# Class_D_Amp.net
KiCad netlist of a schematic drawn in EasyEDA Pro
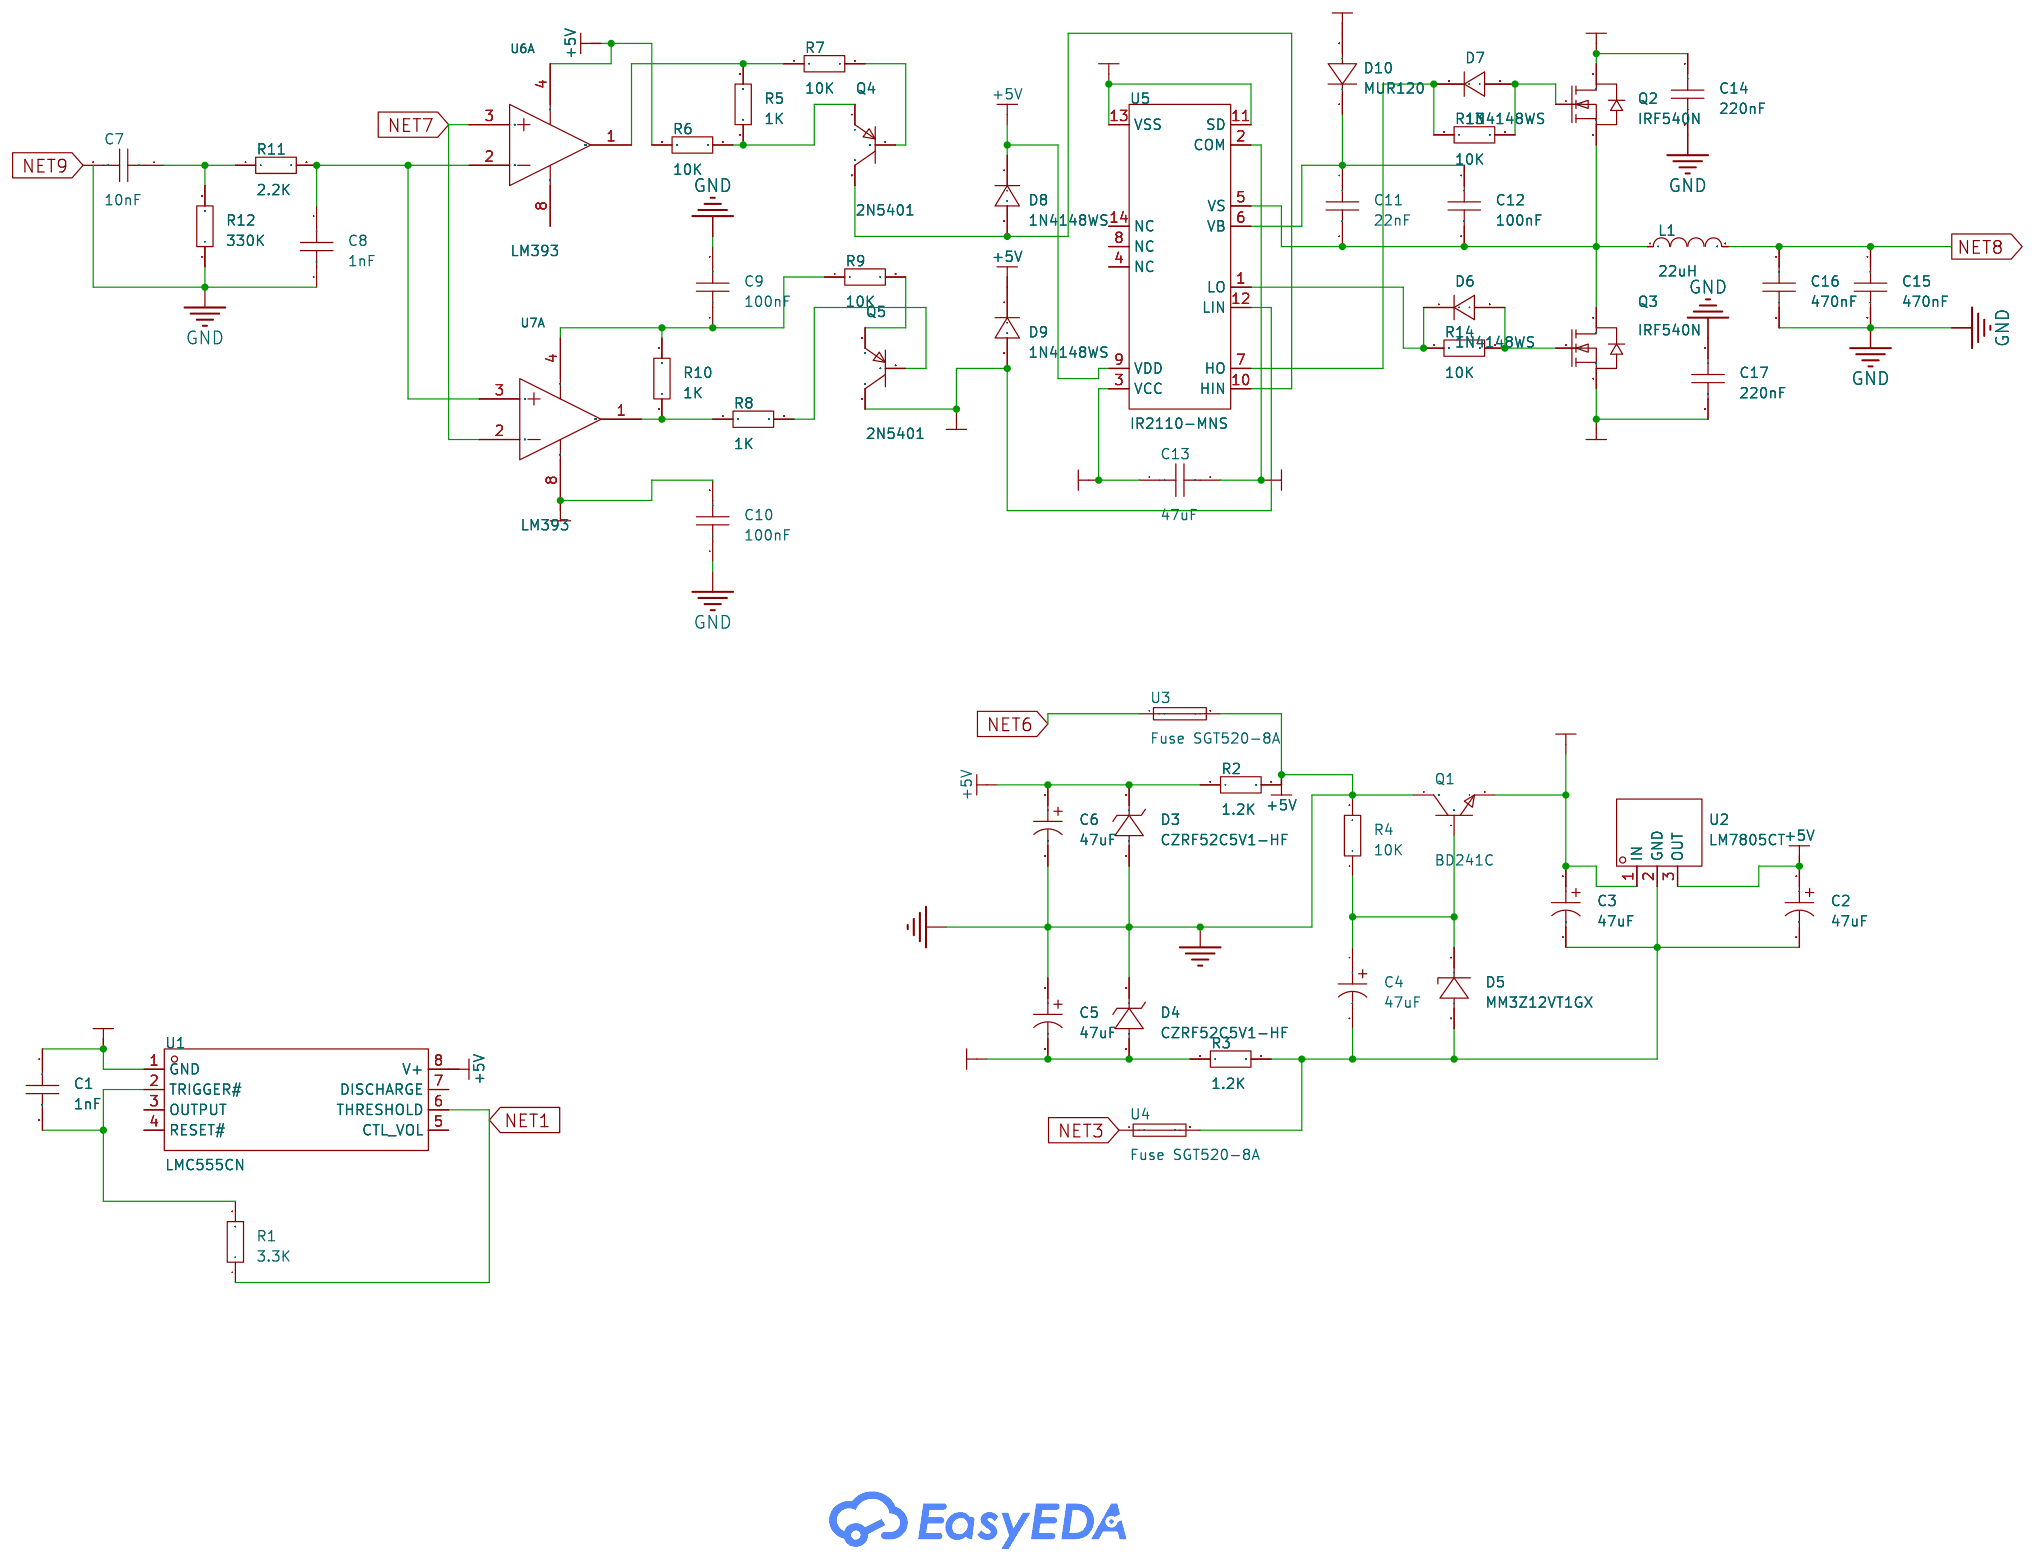
[diagram p0: schematic sheet]

(export (version "E")
  (design (tool "Eeschema 10.0.6"))
  (components
    (comp (ref "C1") (value "1nF") (footprint "easyedapro:C0603") (libsource (lib "easyedapro") (part "CAP")))
    (comp (ref "C2")
      (value "47uF")
      (footprint "easyedapro:CAP-TH_BD6.3-P2.50-D0.6-FD")
      (fields (field (name "Manufacturer Part") "ERA63V47M6X12") (field (name "Manufacturer") "JIERR(捷而瑞)"))
      (libsource (lib "easyedapro") (part "ERA63V47M6X12"))
    )
    (comp (ref "C3")
      (value "47uF")
      (footprint "easyedapro:CAP-TH_BD6.3-P2.50-D0.6-FD")
      (fields (field (name "Manufacturer Part") "ERA63V47M6X12") (field (name "Manufacturer") "JIERR(捷而瑞)"))
      (libsource (lib "easyedapro") (part "ERA63V47M6X12"))
    )
    (comp (ref "C4")
      (value "47uF")
      (footprint "easyedapro:CAP-TH_BD6.3-P2.50-D0.6-FD")
      (fields (field (name "Manufacturer Part") "ERA63V47M6X12") (field (name "Manufacturer") "JIERR(捷而瑞)"))
      (libsource (lib "easyedapro") (part "ERA63V47M6X12"))
    )
    (comp (ref "C5")
      (value "47uF")
      (footprint "easyedapro:CAP-TH_BD6.3-P2.50-D0.6-FD")
      (fields (field (name "Manufacturer Part") "ERA63V47M6X12") (field (name "Manufacturer") "JIERR(捷而瑞)"))
      (libsource (lib "easyedapro") (part "ERA63V47M6X12"))
    )
    (comp (ref "C6")
      (value "47uF")
      (footprint "easyedapro:CAP-TH_BD6.3-P2.50-D0.6-FD")
      (fields (field (name "Manufacturer Part") "ERA63V47M6X12") (field (name "Manufacturer") "JIERR(捷而瑞)"))
      (libsource (lib "easyedapro") (part "ERA63V47M6X12"))
    )
    (comp (ref "C7")
      (value "10nF")
      (footprint "easyedapro:C0603")
      (libsource (lib "easyedapro") (part "CAP"))
    )
    (comp (ref "C8") (value "1nF") (footprint "easyedapro:C0603") (libsource (lib "easyedapro") (part "CAP")))
    (comp (ref "C9")
      (value "100nF")
      (footprint "easyedapro:C0603")
      (libsource (lib "easyedapro") (part "CAP"))
    )
    (comp (ref "C10")
      (value "100nF")
      (footprint "easyedapro:C0603")
      (libsource (lib "easyedapro") (part "CAP"))
    )
    (comp (ref "C11")
      (value "22nF")
      (footprint "easyedapro:C0603")
      (libsource (lib "easyedapro") (part "CAP"))
    )
    (comp (ref "C12")
      (value "100nF")
      (footprint "easyedapro:C0603")
      (libsource (lib "easyedapro") (part "CAP"))
    )
    (comp (ref "C13")
      (value "47uF")
      (footprint "easyedapro:C0603")
      (libsource (lib "easyedapro") (part "CAP"))
    )
    (comp (ref "C14")
      (value "220nF")
      (footprint "easyedapro:C0603")
      (libsource (lib "easyedapro") (part "CAP"))
    )
    (comp (ref "C15")
      (value "470nF")
      (footprint "easyedapro:C0603")
      (libsource (lib "easyedapro") (part "CAP"))
    )
    (comp (ref "C16")
      (value "470nF")
      (footprint "easyedapro:C0603")
      (libsource (lib "easyedapro") (part "CAP"))
    )
    (comp (ref "C17")
      (value "220nF")
      (footprint "easyedapro:C0603")
      (libsource (lib "easyedapro") (part "CAP"))
    )
    (comp (ref "D3")
      (value "CZRF52C5V1-HF")
      (footprint "easyedapro:SOD-323F_L2.5-W1.2-LS2.5-RD")
      (fields (field (name "Manufacturer") "Comchip(典琦)"))
      (libsource (lib "easyedapro") (part "CZRF52C5V1-HF"))
    )
    (comp (ref "D4")
      (value "CZRF52C5V1-HF")
      (footprint "easyedapro:SOD-323F_L2.5-W1.2-LS2.5-RD")
      (fields (field (name "Manufacturer") "Comchip(典琦)"))
      (libsource (lib "easyedapro") (part "CZRF52C5V1-HF"))
    )
    (comp (ref "D5")
      (value "MM3Z12VT1GX")
      (footprint "easyedapro:SOD-323_L1.8-W1.3-LS2.5-RD")
      (fields (field (name "Manufacturer") "Nexperia(安世)"))
      (libsource (lib "easyedapro") (part "MM3Z12VT1GX"))
    )
    (comp (ref "D6")
      (value "1N4148WS")
      (footprint "easyedapro:SOD-323_L1.8-W1.3-LS2.5-RD")
      (fields (field (name "Manufacturer") "CJ(江苏长电/长晶)"))
      (libsource (lib "easyedapro") (part "1N4148WS T4"))
    )
    (comp (ref "D7")
      (value "1N4148WS")
      (footprint "easyedapro:SOD-323_L1.8-W1.3-LS2.5-RD")
      (fields (field (name "Manufacturer") "CJ(江苏长电/长晶)"))
      (libsource (lib "easyedapro") (part "1N4148WS T4"))
    )
    (comp (ref "D8")
      (value "1N4148WS")
      (footprint "easyedapro:SOD-323_L1.8-W1.3-LS2.5-RD")
      (fields (field (name "Manufacturer") "CJ(江苏长电/长晶)"))
      (libsource (lib "easyedapro") (part "1N4148WS T4"))
    )
    (comp (ref "D9")
      (value "1N4148WS")
      (footprint "easyedapro:SOD-323_L1.8-W1.3-LS2.5-RD")
      (fields (field (name "Manufacturer") "CJ(江苏长电/长晶)"))
      (libsource (lib "easyedapro") (part "1N4148WS T4"))
    )
    (comp (ref "D10")
      (value "MUR120")
      (footprint "easyedapro:DO-41_BD2.4-L4.7-P8.70-D0.9-RD")
      (fields (field (name "Manufacturer") "YANGJIE(扬杰)"))
      (libsource (lib "easyedapro") (part "MUR120-C1-0000"))
    )
    (comp (ref "L1") (value "22uH") (footprint "easyedapro:L0603") (libsource (lib "easyedapro") (part "电感")))
    (comp (ref "Q1")
      (value "BD241C")
      (footprint "easyedapro:TO-220-3_L10.0-W4.5-P2.54-L")
      (fields (field (name "Manufacturer") "SPTECH(深圳质超)"))
      (libsource (lib "easyedapro") (part "BD241C"))
    )
    (comp (ref "Q2")
      (value "IRF540N")
      (footprint "easyedapro:TO-220-3_L10.2-W4.6-P2.54-L")
      (fields (field (name "Manufacturer") "DOINGTER(杜因特)"))
      (libsource (lib "easyedapro") (part "IRF540N_C41430602"))
    )
    (comp (ref "Q3")
      (value "IRF540N")
      (footprint "easyedapro:TO-220-3_L10.2-W4.6-P2.54-L")
      (fields (field (name "Manufacturer") "DOINGTER(杜因特)"))
      (libsource (lib "easyedapro") (part "IRF540N_C41430602"))
    )
    (comp (ref "Q4")
      (value "2N5401")
      (footprint "easyedapro:TO-92-3_L4.5-W3.5-P1.27-L")
      (fields (field (name "Manufacturer") "Slkor(萨科微)"))
      (libsource (lib "easyedapro") (part "2N5401_C2936033"))
    )
    (comp (ref "Q5")
      (value "2N5401")
      (footprint "easyedapro:TO-92-3_L4.5-W3.5-P1.27-L")
      (fields (field (name "Manufacturer") "Slkor(萨科微)"))
      (libsource (lib "easyedapro") (part "2N5401_C2936033"))
    )
    (comp (ref "R1")
      (value "3.3K")
      (footprint "easyedapro:R0603")
      (libsource (lib "easyedapro") (part "Res"))
    )
    (comp (ref "R2")
      (value "1.2K")
      (footprint "easyedapro:R0603")
      (libsource (lib "easyedapro") (part "Res"))
    )
    (comp (ref "R3")
      (value "1.2K")
      (footprint "easyedapro:R0603")
      (libsource (lib "easyedapro") (part "Res"))
    )
    (comp (ref "R4") (value "10K") (footprint "easyedapro:R0603") (libsource (lib "easyedapro") (part "Res")))
    (comp (ref "R5") (value "1K") (footprint "easyedapro:R0603") (libsource (lib "easyedapro") (part "Res")))
    (comp (ref "R6") (value "10K") (footprint "easyedapro:R0603") (libsource (lib "easyedapro") (part "Res")))
    (comp (ref "R7") (value "10K") (footprint "easyedapro:R0603") (libsource (lib "easyedapro") (part "Res")))
    (comp (ref "R8") (value "1K") (footprint "easyedapro:R0603") (libsource (lib "easyedapro") (part "Res")))
    (comp (ref "R9") (value "10K") (footprint "easyedapro:R0603") (libsource (lib "easyedapro") (part "Res")))
    (comp (ref "R10") (value "1K") (footprint "easyedapro:R0603") (libsource (lib "easyedapro") (part "Res")))
    (comp (ref "R11")
      (value "2.2K")
      (footprint "easyedapro:R0603")
      (libsource (lib "easyedapro") (part "Res"))
    )
    (comp (ref "R12")
      (value "330K")
      (footprint "easyedapro:R0603")
      (libsource (lib "easyedapro") (part "Res"))
    )
    (comp (ref "R13")
      (value "10K")
      (footprint "easyedapro:R0603")
      (libsource (lib "easyedapro") (part "Res"))
    )
    (comp (ref "R14")
      (value "10K")
      (footprint "easyedapro:R0603")
      (libsource (lib "easyedapro") (part "Res"))
    )
    (comp (ref "U1")
      (value "LMC555CN")
      (footprint "easyedapro:DIP-8_L9.7-W6.4-P2.54-LS7.6-BL")
      (description "Operating Temperature:-40°C~+85°C Operating Temperature:-40°C~+85°C")
      (fields (field (name "Manufacturer") "TI(德州仪器)"))
      (libsource (lib "easyedapro") (part "LMC555CN"))
    )
    (comp (ref "U2")
      (value "LM7805CT")
      (footprint "easyedapro:TO-220-3_L10.0-W4.5-P2.54-L")
      (libsource (lib "easyedapro") (part "LM7805CT"))
    )
    (comp (ref "U3")
      (value "Fuse SGT520-8A")
      (footprint "easyedapro:FUSE-SMD_L20.0-W5.2")
      (fields (field (name "Manufacturer") "SET(赛尔特)"))
      (libsource (lib "easyedapro") (part "FUSE SGT520-8A"))
    )
    (comp (ref "U4")
      (value "Fuse SGT520-8A")
      (footprint "easyedapro:FUSE-SMD_L20.0-W5.2")
      (fields (field (name "Manufacturer") "SET(赛尔特)"))
      (libsource (lib "easyedapro") (part "FUSE SGT520-8A"))
    )
    (comp (ref "U5")
      (value "IR2110-MNS")
      (footprint "easyedapro:PDIP-14_L19.2-W6.6-P2.54-LS7.6-BL")
      (fields (field (name "Manufacturer") "minos(迈诺斯)"))
      (libsource (lib "easyedapro") (part "IR2110-MNS"))
    )
    (comp (ref "U6")
      (value "LM393")
      (footprint "easyedapro:SOP-8_L4.9-W3.9-P1.27-LS6.0-BL")
      (fields (field (name "Manufacturer") "MSKSEMI(美森科)"))
      (libsource (lib "easyedapro") (part "LM393_C5252905"))
    )
    (comp (ref "U7")
      (value "LM393")
      (footprint "easyedapro:SOP-8_L4.9-W3.9-P1.27-LS6.0-BL")
      (fields (field (name "Manufacturer") "MSKSEMI(美森科)"))
      (libsource (lib "easyedapro") (part "LM393_C5252905"))
    )
  )
  (nets
    (net (code "1") (name "+5V") (class "Default")
      (node (ref "C2") (pin "1") (pinfunction "1_1") (pintype "input"))
      (node (ref "C5") (pin "1") (pinfunction "1_1") (pintype "input"))
      (node (ref "C6") (pin "1") (pinfunction "1_1") (pintype "input"))
      (node (ref "C6") (pin "2") (pinfunction "2_2") (pintype "input"))
      (node (ref "D3") (pin "1") (pinfunction "K_1") (pintype "unspecified"))
      (node (ref "D3") (pin "2") (pinfunction "A_2") (pintype "unspecified"))
      (node (ref "D4") (pin "1") (pinfunction "K_1") (pintype "unspecified"))
      (node (ref "D8") (pin "1") (pinfunction "K_1") (pintype "unspecified"))
      (node (ref "D9") (pin "1") (pinfunction "K_1") (pintype "unspecified"))
      (node (ref "Q1") (pin "2") (pinfunction "C_2") (pintype "input"))
      (node (ref "R2") (pin "1") (pinfunction "1_1") (pintype "input"))
      (node (ref "R2") (pin "2") (pinfunction "2_2") (pintype "input"))
      (node (ref "R4") (pin "2") (pinfunction "2_2") (pintype "input"))
      (node (ref "R6") (pin "1") (pinfunction "1_1") (pintype "input"))
      (node (ref "U1") (pin "8") (pinfunction "V+_8") (pintype "unspecified"))
      (node (ref "U2") (pin "3") (pinfunction "OUT_3") (pintype "unspecified"))
      (node (ref "U3") (pin "2") (pinfunction "2_2") (pintype "unspecified"))
      (node (ref "U5") (pin "9") (pinfunction "VDD_9") (pintype "unspecified"))
      (node (ref "U6") (pin "4") (pinfunction "VEE_4") (pintype "input"))
    )
    (net (code "2") (name "+12V") (class "Default")
      (node (ref "C13") (pin "1") (pinfunction "1_1") (pintype "input"))
      (node (ref "C3") (pin "1") (pinfunction "1_1") (pintype "input"))
      (node (ref "D10") (pin "2") (pinfunction "A_2") (pintype "unspecified"))
      (node (ref "Q1") (pin "3") (pinfunction "E_3") (pintype "input"))
      (node (ref "U2") (pin "1") (pinfunction "IN_1") (pintype "unspecified"))
      (node (ref "U5") (pin "3") (pinfunction "VCC_3") (pintype "unspecified"))
    )
    (net (code "3") (name "+30V") (class "Default")
      (node (ref "C14") (pin "1") (pinfunction "1_1") (pintype "input"))
      (node (ref "Q2") (pin "2") (pinfunction "D_2") (pintype "unspecified"))
    )
    (net (code "4") (name "-5V") (class "Default")
      (node (ref "C1") (pin "1") (pinfunction "1_1") (pintype "input"))
      (node (ref "C10") (pin "2") (pinfunction "2_2") (pintype "input"))
      (node (ref "C5") (pin "2") (pinfunction "2_2") (pintype "input"))
      (node (ref "D4") (pin "2") (pinfunction "A_2") (pintype "unspecified"))
      (node (ref "R3") (pin "1") (pinfunction "1_1") (pintype "input"))
      (node (ref "U1") (pin "1") (pinfunction "GND_1") (pintype "unspecified"))
      (node (ref "U7") (pin "8") (pinfunction "VCC_8") (pintype "input"))
    )
    (net (code "5") (name "-30V") (class "Default")
      (node (ref "C13") (pin "2") (pinfunction "2_2") (pintype "input"))
      (node (ref "C17") (pin "2") (pinfunction "2_2") (pintype "input"))
      (node (ref "D9") (pin "2") (pinfunction "A_2") (pintype "unspecified"))
      (node (ref "Q3") (pin "3") (pinfunction "S_3") (pintype "unspecified"))
      (node (ref "Q5") (pin "3") (pinfunction "C_3") (pintype "input"))
      (node (ref "U5") (pin "11") (pinfunction "SD_11") (pintype "unspecified"))
      (node (ref "U5") (pin "12") (pinfunction "LIN_12") (pintype "unspecified"))
      (node (ref "U5") (pin "13") (pinfunction "VSS_13") (pintype "unspecified"))
      (node (ref "U5") (pin "2") (pinfunction "COM_2") (pintype "unspecified"))
    )
    (net (code "6") (name "GND") (class "Default")
      (node (ref "C10") (pin "1") (pinfunction "1_1") (pintype "input"))
      (node (ref "C14") (pin "2") (pinfunction "2_2") (pintype "input"))
      (node (ref "C15") (pin "2") (pinfunction "2_2") (pintype "input"))
      (node (ref "C16") (pin "2") (pinfunction "2_2") (pintype "input"))
      (node (ref "C17") (pin "1") (pinfunction "1_1") (pintype "input"))
      (node (ref "C8") (pin "2") (pinfunction "2_2") (pintype "input"))
      (node (ref "C9") (pin "2") (pinfunction "2_2") (pintype "input"))
      (node (ref "R12") (pin "1") (pinfunction "1_1") (pintype "input"))
    )
    (net (code "7") (name "NET1") (class "Default")
      (node (ref "R1") (pin "1") (pinfunction "1_1") (pintype "input"))
      (node (ref "U1") (pin "6") (pinfunction "THRESHOLD_6") (pintype "unspecified"))
    )
    (net (code "8") (name "NET3") (class "Default")
      (node (ref "U4") (pin "1") (pinfunction "1_1") (pintype "unspecified"))
    )
    (net (code "9") (name "NET6") (class "Default")
      (node (ref "U3") (pin "1") (pinfunction "1_1") (pintype "unspecified"))
    )
    (net (code "10") (name "NET7") (class "Default")
      (node (ref "U6") (pin "3") (pinfunction "1IN+_3") (pintype "input"))
      (node (ref "U7") (pin "2") (pinfunction "1IN-_2") (pintype "input"))
    )
    (net (code "11") (name "NET8") (class "Default")
      (node (ref "C15") (pin "1") (pinfunction "1_1") (pintype "input"))
      (node (ref "C16") (pin "1") (pinfunction "1_1") (pintype "input"))
      (node (ref "L1") (pin "2") (pinfunction "2_2") (pintype "input"))
    )
    (net (code "12") (name "NET9") (class "Default")
      (node (ref "C7") (pin "2") (pinfunction "2_2") (pintype "input"))
    )
    (net (code "13") (name "Net-(C7-Pad1)") (class "Default")
      (node (ref "C7") (pin "1") (pinfunction "1_1") (pintype "input"))
      (node (ref "R11") (pin "1") (pinfunction "1_1") (pintype "input"))
      (node (ref "R12") (pin "2") (pinfunction "2_2") (pintype "input"))
    )
    (net (code "14") (name "Net-(D5-A)") (class "Default")
      (node (ref "C2") (pin "2") (pinfunction "2_2") (pintype "input"))
      (node (ref "C3") (pin "2") (pinfunction "2_2") (pintype "input"))
      (node (ref "C4") (pin "2") (pinfunction "2_2") (pintype "input"))
      (node (ref "D5") (pin "2") (pinfunction "A_2") (pintype "unspecified"))
      (node (ref "R3") (pin "2") (pinfunction "2_2") (pintype "input"))
      (node (ref "U2") (pin "2") (pinfunction "GND_2") (pintype "unspecified"))
      (node (ref "U4") (pin "2") (pinfunction "2_2") (pintype "unspecified"))
    )
    (net (code "15") (name "Net-(D5-K)") (class "Default")
      (node (ref "C4") (pin "1") (pinfunction "1_1") (pintype "input"))
      (node (ref "D5") (pin "1") (pinfunction "K_1") (pintype "unspecified"))
      (node (ref "Q1") (pin "1") (pinfunction "B_1") (pintype "input"))
      (node (ref "R4") (pin "1") (pinfunction "1_1") (pintype "input"))
    )
    (net (code "16") (name "Net-(D6-A)") (class "Default")
      (node (ref "D6") (pin "2") (pinfunction "A_2") (pintype "unspecified"))
      (node (ref "Q3") (pin "1") (pinfunction "G_1") (pintype "unspecified"))
      (node (ref "R14") (pin "2") (pinfunction "2_2") (pintype "input"))
    )
    (net (code "17") (name "Net-(D6-K)") (class "Default")
      (node (ref "D6") (pin "1") (pinfunction "K_1") (pintype "unspecified"))
      (node (ref "R14") (pin "1") (pinfunction "1_1") (pintype "input"))
      (node (ref "U5") (pin "1") (pinfunction "LO_1") (pintype "unspecified"))
    )
    (net (code "18") (name "Net-(D7-A)") (class "Default")
      (node (ref "D7") (pin "2") (pinfunction "A_2") (pintype "unspecified"))
      (node (ref "Q2") (pin "1") (pinfunction "G_1") (pintype "unspecified"))
      (node (ref "R13") (pin "2") (pinfunction "2_2") (pintype "input"))
    )
    (net (code "19") (name "Net-(D7-K)") (class "Default")
      (node (ref "D7") (pin "1") (pinfunction "K_1") (pintype "unspecified"))
      (node (ref "R13") (pin "1") (pinfunction "1_1") (pintype "input"))
      (node (ref "U5") (pin "7") (pinfunction "HO_7") (pintype "unspecified"))
    )
    (net (code "20") (name "Net-(D8-A)") (class "Default")
      (node (ref "D8") (pin "2") (pinfunction "A_2") (pintype "unspecified"))
      (node (ref "Q4") (pin "3") (pinfunction "C_3") (pintype "input"))
      (node (ref "U5") (pin "10") (pinfunction "HIN_10") (pintype "unspecified"))
    )
    (net (code "21") (name "Net-(D10-K)") (class "Default")
      (node (ref "C11") (pin "1") (pinfunction "1_1") (pintype "input"))
      (node (ref "C12") (pin "1") (pinfunction "1_1") (pintype "input"))
      (node (ref "D10") (pin "1") (pinfunction "K_1") (pintype "unspecified"))
      (node (ref "U5") (pin "6") (pinfunction "VB_6") (pintype "unspecified"))
    )
    (net (code "22") (name "Net-(Q2-S)") (class "Default")
      (node (ref "C11") (pin "2") (pinfunction "2_2") (pintype "input"))
      (node (ref "C12") (pin "2") (pinfunction "2_2") (pintype "input"))
      (node (ref "L1") (pin "1") (pinfunction "1_1") (pintype "input"))
      (node (ref "Q2") (pin "3") (pinfunction "S_3") (pintype "unspecified"))
      (node (ref "Q3") (pin "2") (pinfunction "D_2") (pintype "unspecified"))
      (node (ref "U5") (pin "5") (pinfunction "VS_5") (pintype "unspecified"))
    )
    (net (code "23") (name "Net-(Q4-B)") (class "Default")
      (node (ref "Q4") (pin "2") (pinfunction "B_2") (pintype "input"))
      (node (ref "R7") (pin "2") (pinfunction "2_2") (pintype "input"))
    )
    (net (code "24") (name "Net-(Q4-E)") (class "Default")
      (node (ref "Q4") (pin "1") (pinfunction "E_1") (pintype "input"))
      (node (ref "R5") (pin "1") (pinfunction "1_1") (pintype "input"))
      (node (ref "R6") (pin "2") (pinfunction "2_2") (pintype "input"))
    )
    (net (code "25") (name "Net-(Q5-B)") (class "Default")
      (node (ref "Q5") (pin "2") (pinfunction "B_2") (pintype "input"))
      (node (ref "R8") (pin "2") (pinfunction "2_2") (pintype "input"))
    )
    (net (code "26") (name "Net-(Q5-E)") (class "Default")
      (node (ref "Q5") (pin "1") (pinfunction "E_1") (pintype "input"))
      (node (ref "R9") (pin "2") (pinfunction "2_2") (pintype "input"))
    )
    (net (code "27") (name "Net-(U1-TRIGGER#)") (class "Default")
      (node (ref "C1") (pin "2") (pinfunction "2_2") (pintype "input"))
      (node (ref "R1") (pin "2") (pinfunction "2_2") (pintype "input"))
      (node (ref "U1") (pin "2") (pinfunction "TRIGGER#_2") (pintype "unspecified"))
    )
    (net (code "28") (name "Net-(U6A-1IN-)") (class "Default")
      (node (ref "C8") (pin "1") (pinfunction "1_1") (pintype "input"))
      (node (ref "R11") (pin "2") (pinfunction "2_2") (pintype "input"))
      (node (ref "U6") (pin "2") (pinfunction "1IN-_2") (pintype "input"))
      (node (ref "U7") (pin "3") (pinfunction "1IN+_3") (pintype "input"))
    )
    (net (code "29") (name "Net-(U6A-1OUT1)") (class "Default")
      (node (ref "R5") (pin "2") (pinfunction "2_2") (pintype "input"))
      (node (ref "R7") (pin "1") (pinfunction "1_1") (pintype "input"))
      (node (ref "U6") (pin "1") (pinfunction "1OUT1_1") (pintype "output"))
    )
    (net (code "30") (name "Net-(U7A-1OUT1)") (class "Default")
      (node (ref "R10") (pin "1") (pinfunction "1_1") (pintype "input"))
      (node (ref "R8") (pin "1") (pinfunction "1_1") (pintype "input"))
      (node (ref "U7") (pin "1") (pinfunction "1OUT1_1") (pintype "output"))
    )
    (net (code "31") (name "Net-(U7A-VEE)") (class "Default")
      (node (ref "C9") (pin "1") (pinfunction "1_1") (pintype "input"))
      (node (ref "R10") (pin "2") (pinfunction "2_2") (pintype "input"))
      (node (ref "R9") (pin "1") (pinfunction "1_1") (pintype "input"))
      (node (ref "U7") (pin "4") (pinfunction "VEE_4") (pintype "input"))
    )
    (net (code "32") (name "unconnected-(U1-CTL_VOL-Pad5)") (class "Default")
      (node (ref "U1") (pin "5") (pinfunction "CTL_VOL_5") (pintype "unspecified"))
    )
    (net (code "33") (name "unconnected-(U1-DISCHARGE-Pad7)") (class "Default")
      (node (ref "U1") (pin "7") (pinfunction "DISCHARGE_7") (pintype "unspecified"))
    )
    (net (code "34") (name "unconnected-(U1-OUTPUT-Pad3)") (class "Default")
      (node (ref "U1") (pin "3") (pinfunction "OUTPUT_3") (pintype "unspecified"))
    )
    (net (code "35") (name "unconnected-(U1-RESET#-Pad4)") (class "Default")
      (node (ref "U1") (pin "4") (pinfunction "RESET#_4") (pintype "unspecified"))
    )
    (net (code "36") (name "unconnected-(U5-NC-Pad4)") (class "Default")
      (node (ref "U5") (pin "4") (pinfunction "NC_4") (pintype "unspecified"))
    )
    (net (code "37") (name "unconnected-(U5-NC-Pad8)") (class "Default")
      (node (ref "U5") (pin "8") (pinfunction "NC_8") (pintype "unspecified"))
    )
    (net (code "38") (name "unconnected-(U5-NC-Pad14)") (class "Default")
      (node (ref "U5") (pin "14") (pinfunction "NC_14") (pintype "unspecified"))
    )
    (net (code "39") (name "unconnected-(U6A-VCC-Pad8)") (class "Default")
      (node (ref "U6") (pin "8") (pinfunction "VCC_8") (pintype "input"))
    )
  )
)
